# 20250808.net
KiCad netlist of a schematic drawn in EasyEDA Pro
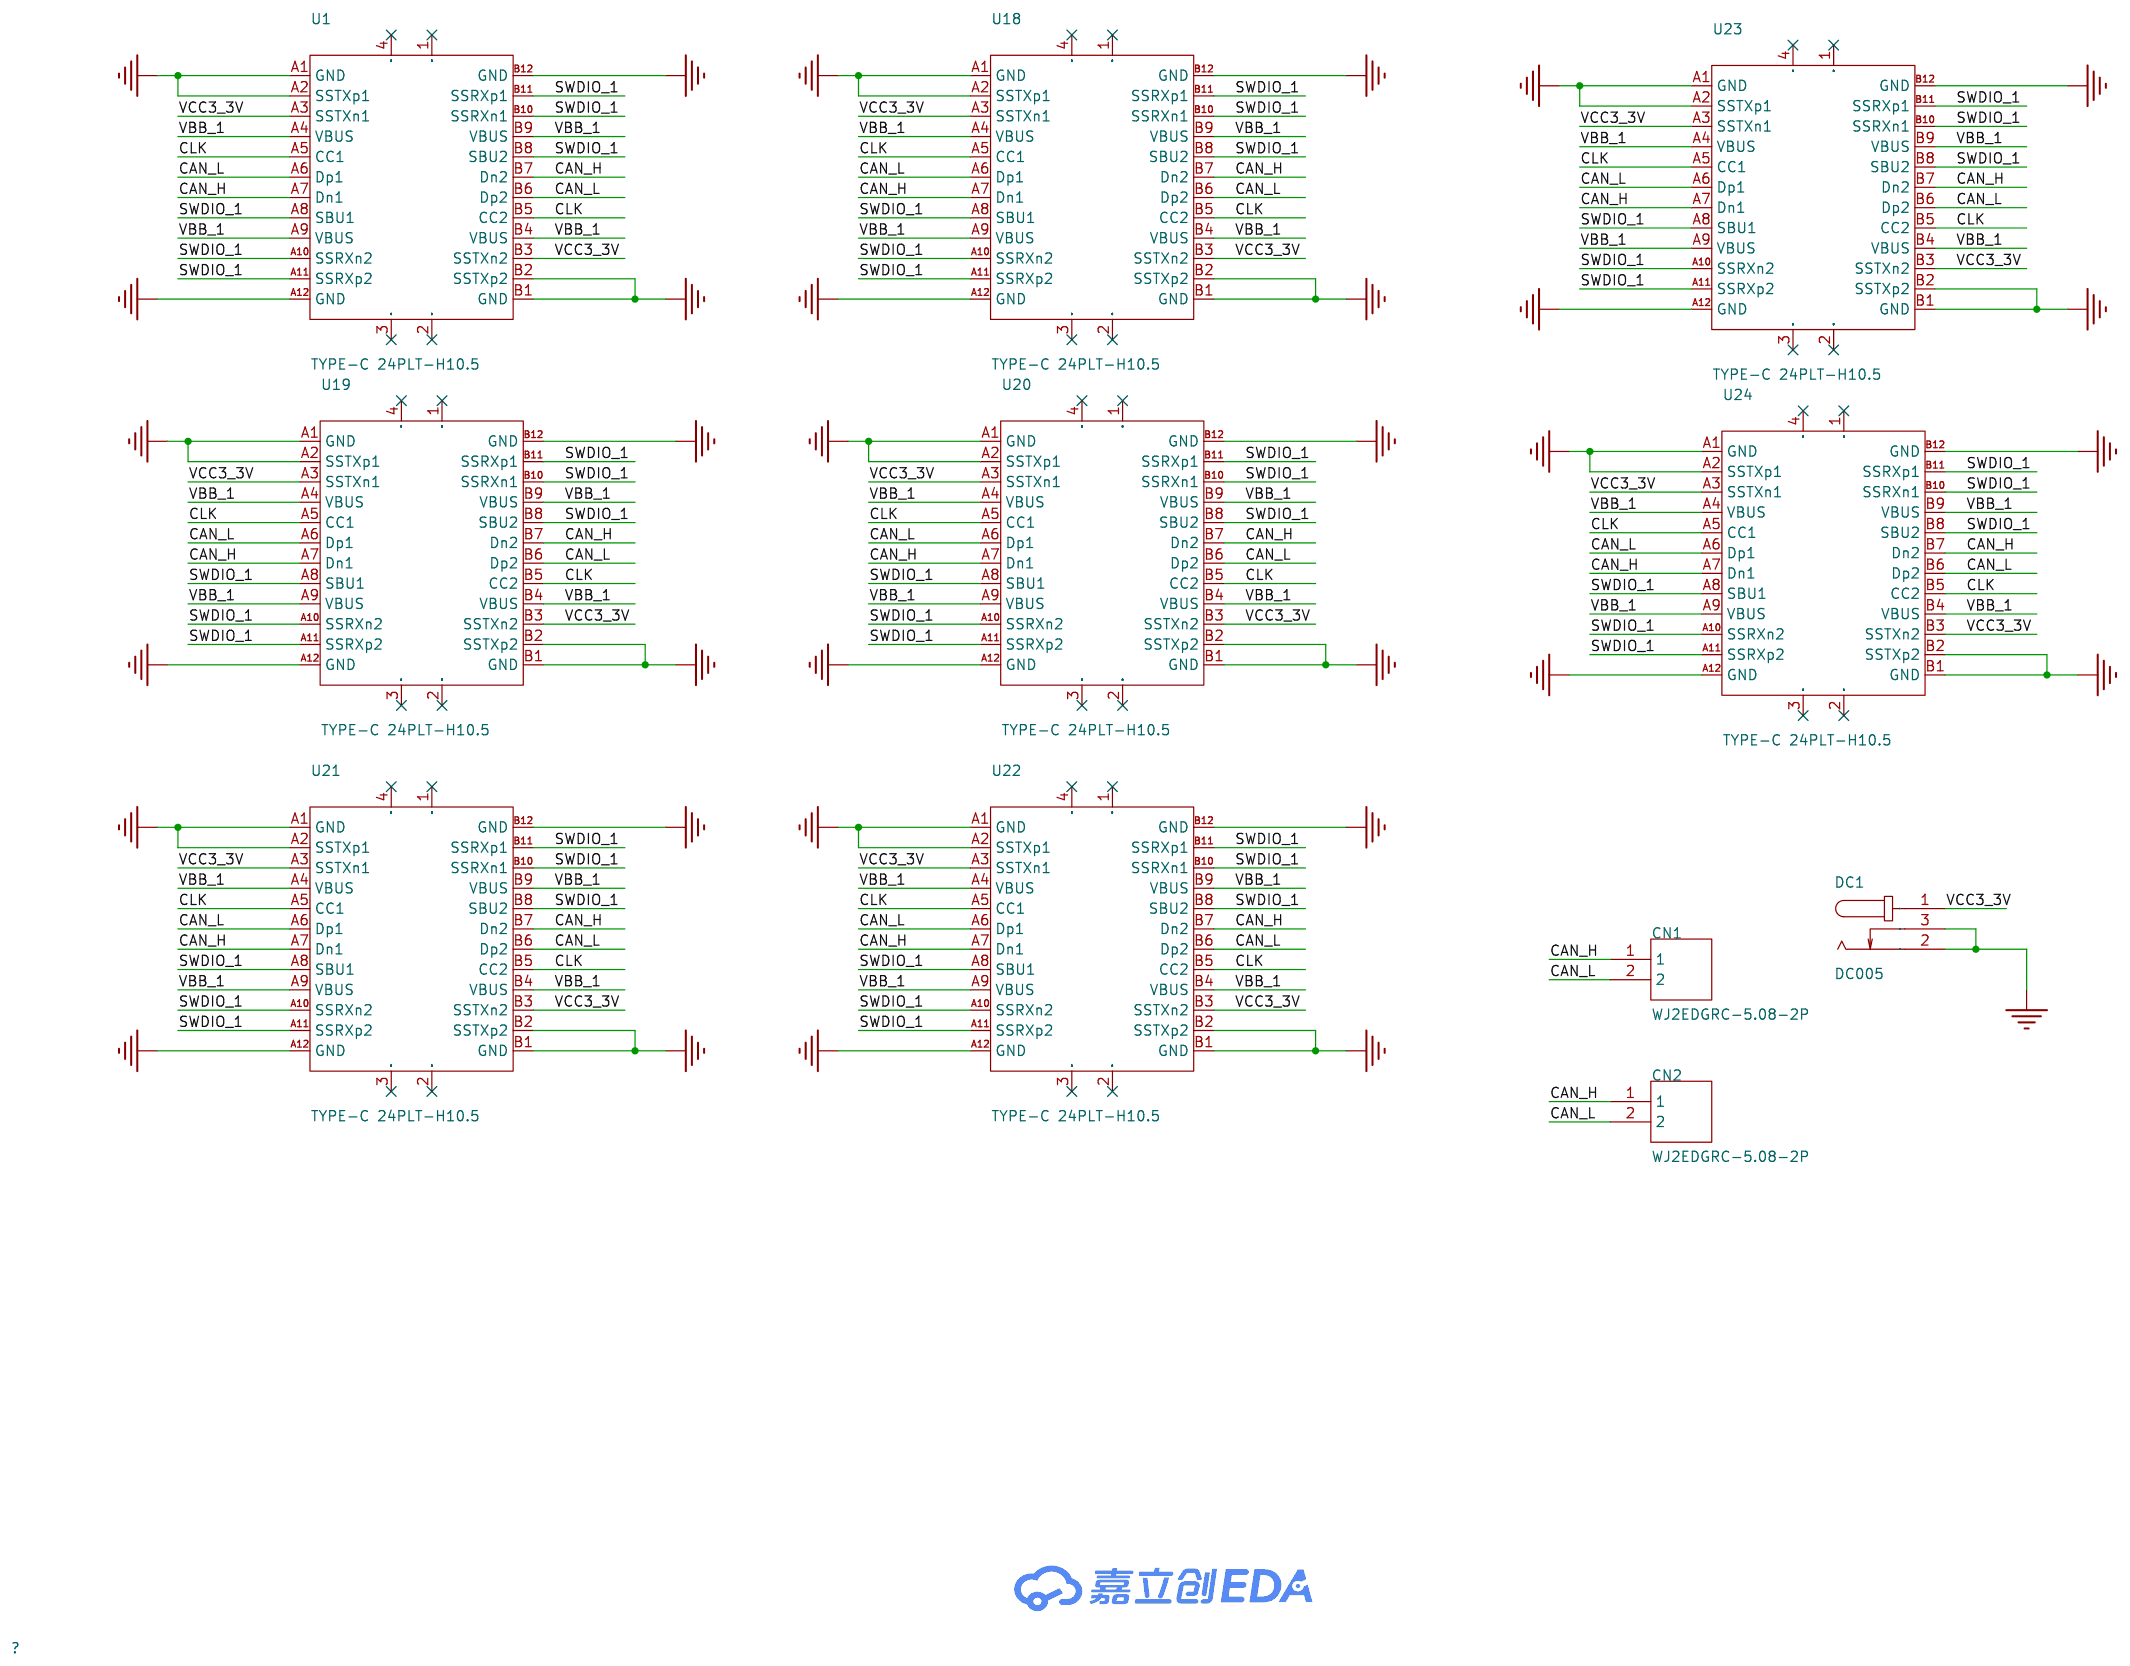
[diagram p0: schematic sheet]

(export (version "E")
  (design (tool "Eeschema 10.0.6"))
  (components
    (comp (ref "CN1")
      (value "WJ2EDGRC-5.08-2P")
      (footprint "easyedapro:CONN-TH_2P-P5.08_WJ2EDGRC-5.08-2P")
      (fields (field (name "Manufacturer") "KANGNEX(康奈克斯电气)"))
      (libsource (lib "easyedapro") (part "WJ2EDGRC-5.08-2P"))
    )
    (comp (ref "CN2")
      (value "WJ2EDGRC-5.08-2P")
      (footprint "easyedapro:CONN-TH_2P-P5.08_WJ2EDGRC-5.08-2P")
      (fields (field (name "Manufacturer") "KANGNEX(康奈克斯电气)"))
      (libsource (lib "easyedapro") (part "WJ2EDGRC-5.08-2P"))
    )
    (comp (ref "DC1")
      (value "DC005")
      (footprint "easyedapro:DC-IN-TH_DC005")
      (description "连接器类型:DC电源插座;安装方式:弯插;触点内径:2mm;触点外径:6.3mm;额定电流:500mA;额定电压:30V;工作温度范围:-25°C~+70°C;")
      (fields (field (name "Manufacturer") "SHOU HAN(首韩)"))
      (libsource (lib "easyedapro") (part "DC005_C431533"))
    )
    (comp (ref "U1")
      (value "TYPE-C 24PLT-H10.5")
      (footprint "easyedapro:USB-C_TYPE-C-24PLT-H10.5-1")
      (fields (field (name "Manufacturer") "SHOU HAN(首韩)"))
      (libsource (lib "easyedapro") (part "TYPE-C 24PLT-H10.5"))
    )
    (comp (ref "U18")
      (value "TYPE-C 24PLT-H10.5")
      (footprint "easyedapro:USB-C_TYPE-C-24PLT-H10.5-1")
      (fields (field (name "Manufacturer") "SHOU HAN(首韩)"))
      (libsource (lib "easyedapro") (part "TYPE-C 24PLT-H10.5"))
    )
    (comp (ref "U19")
      (value "TYPE-C 24PLT-H10.5")
      (footprint "easyedapro:USB-C_TYPE-C-24PLT-H10.5-1")
      (fields (field (name "Manufacturer") "SHOU HAN(首韩)"))
      (libsource (lib "easyedapro") (part "TYPE-C 24PLT-H10.5"))
    )
    (comp (ref "U20")
      (value "TYPE-C 24PLT-H10.5")
      (footprint "easyedapro:USB-C_TYPE-C-24PLT-H10.5-1")
      (fields (field (name "Manufacturer") "SHOU HAN(首韩)"))
      (libsource (lib "easyedapro") (part "TYPE-C 24PLT-H10.5"))
    )
    (comp (ref "U21")
      (value "TYPE-C 24PLT-H10.5")
      (footprint "easyedapro:USB-C_TYPE-C-24PLT-H10.5-1")
      (fields (field (name "Manufacturer") "SHOU HAN(首韩)"))
      (libsource (lib "easyedapro") (part "TYPE-C 24PLT-H10.5"))
    )
    (comp (ref "U22")
      (value "TYPE-C 24PLT-H10.5")
      (footprint "easyedapro:USB-C_TYPE-C-24PLT-H10.5-1")
      (fields (field (name "Manufacturer") "SHOU HAN(首韩)"))
      (libsource (lib "easyedapro") (part "TYPE-C 24PLT-H10.5"))
    )
    (comp (ref "U23")
      (value "TYPE-C 24PLT-H10.5")
      (footprint "easyedapro:USB-C_TYPE-C-24PLT-H10.5-1")
      (fields (field (name "Manufacturer") "SHOU HAN(首韩)"))
      (libsource (lib "easyedapro") (part "TYPE-C 24PLT-H10.5"))
    )
    (comp (ref "U24")
      (value "TYPE-C 24PLT-H10.5")
      (footprint "easyedapro:USB-C_TYPE-C-24PLT-H10.5-1")
      (fields (field (name "Manufacturer") "SHOU HAN(首韩)"))
      (libsource (lib "easyedapro") (part "TYPE-C 24PLT-H10.5"))
    )
  )
  (nets
    (net (code "1") (name "/CAN_H") (class "Default")
      (node (ref "CN1") (pin "1") (pinfunction "1_1") (pintype "unspecified"))
      (node (ref "CN2") (pin "1") (pinfunction "1_1") (pintype "unspecified"))
      (node (ref "U1") (pin "A7") (pinfunction "Dn1_A7") (pintype "unspecified"))
      (node (ref "U1") (pin "B7") (pinfunction "Dn2_B7") (pintype "unspecified"))
      (node (ref "U18") (pin "A7") (pinfunction "Dn1_A7") (pintype "unspecified"))
      (node (ref "U18") (pin "B7") (pinfunction "Dn2_B7") (pintype "unspecified"))
      (node (ref "U19") (pin "A7") (pinfunction "Dn1_A7") (pintype "unspecified"))
      (node (ref "U19") (pin "B7") (pinfunction "Dn2_B7") (pintype "unspecified"))
      (node (ref "U20") (pin "A7") (pinfunction "Dn1_A7") (pintype "unspecified"))
      (node (ref "U20") (pin "B7") (pinfunction "Dn2_B7") (pintype "unspecified"))
      (node (ref "U21") (pin "A7") (pinfunction "Dn1_A7") (pintype "unspecified"))
      (node (ref "U21") (pin "B7") (pinfunction "Dn2_B7") (pintype "unspecified"))
      (node (ref "U22") (pin "A7") (pinfunction "Dn1_A7") (pintype "unspecified"))
      (node (ref "U22") (pin "B7") (pinfunction "Dn2_B7") (pintype "unspecified"))
      (node (ref "U23") (pin "A7") (pinfunction "Dn1_A7") (pintype "unspecified"))
      (node (ref "U23") (pin "B7") (pinfunction "Dn2_B7") (pintype "unspecified"))
      (node (ref "U24") (pin "A7") (pinfunction "Dn1_A7") (pintype "unspecified"))
      (node (ref "U24") (pin "B7") (pinfunction "Dn2_B7") (pintype "unspecified"))
    )
    (net (code "2") (name "/CAN_L") (class "Default")
      (node (ref "CN1") (pin "2") (pinfunction "2_2") (pintype "unspecified"))
      (node (ref "CN2") (pin "2") (pinfunction "2_2") (pintype "unspecified"))
      (node (ref "U1") (pin "A6") (pinfunction "Dp1_A6") (pintype "unspecified"))
      (node (ref "U1") (pin "B6") (pinfunction "Dp2_B6") (pintype "unspecified"))
      (node (ref "U18") (pin "A6") (pinfunction "Dp1_A6") (pintype "unspecified"))
      (node (ref "U18") (pin "B6") (pinfunction "Dp2_B6") (pintype "unspecified"))
      (node (ref "U19") (pin "A6") (pinfunction "Dp1_A6") (pintype "unspecified"))
      (node (ref "U19") (pin "B6") (pinfunction "Dp2_B6") (pintype "unspecified"))
      (node (ref "U20") (pin "A6") (pinfunction "Dp1_A6") (pintype "unspecified"))
      (node (ref "U20") (pin "B6") (pinfunction "Dp2_B6") (pintype "unspecified"))
      (node (ref "U21") (pin "A6") (pinfunction "Dp1_A6") (pintype "unspecified"))
      (node (ref "U21") (pin "B6") (pinfunction "Dp2_B6") (pintype "unspecified"))
      (node (ref "U22") (pin "A6") (pinfunction "Dp1_A6") (pintype "unspecified"))
      (node (ref "U22") (pin "B6") (pinfunction "Dp2_B6") (pintype "unspecified"))
      (node (ref "U23") (pin "A6") (pinfunction "Dp1_A6") (pintype "unspecified"))
      (node (ref "U23") (pin "B6") (pinfunction "Dp2_B6") (pintype "unspecified"))
      (node (ref "U24") (pin "A6") (pinfunction "Dp1_A6") (pintype "unspecified"))
      (node (ref "U24") (pin "B6") (pinfunction "Dp2_B6") (pintype "unspecified"))
    )
    (net (code "3") (name "/CLK") (class "Default")
      (node (ref "U1") (pin "A5") (pinfunction "CC1_A5") (pintype "unspecified"))
      (node (ref "U1") (pin "B5") (pinfunction "CC2_B5") (pintype "unspecified"))
      (node (ref "U18") (pin "A5") (pinfunction "CC1_A5") (pintype "unspecified"))
      (node (ref "U18") (pin "B5") (pinfunction "CC2_B5") (pintype "unspecified"))
      (node (ref "U19") (pin "A5") (pinfunction "CC1_A5") (pintype "unspecified"))
      (node (ref "U19") (pin "B5") (pinfunction "CC2_B5") (pintype "unspecified"))
      (node (ref "U20") (pin "A5") (pinfunction "CC1_A5") (pintype "unspecified"))
      (node (ref "U20") (pin "B5") (pinfunction "CC2_B5") (pintype "unspecified"))
      (node (ref "U21") (pin "A5") (pinfunction "CC1_A5") (pintype "unspecified"))
      (node (ref "U21") (pin "B5") (pinfunction "CC2_B5") (pintype "unspecified"))
      (node (ref "U22") (pin "A5") (pinfunction "CC1_A5") (pintype "unspecified"))
      (node (ref "U22") (pin "B5") (pinfunction "CC2_B5") (pintype "unspecified"))
      (node (ref "U23") (pin "A5") (pinfunction "CC1_A5") (pintype "unspecified"))
      (node (ref "U23") (pin "B5") (pinfunction "CC2_B5") (pintype "unspecified"))
      (node (ref "U24") (pin "A5") (pinfunction "CC1_A5") (pintype "unspecified"))
      (node (ref "U24") (pin "B5") (pinfunction "CC2_B5") (pintype "unspecified"))
    )
    (net (code "4") (name "/SWDIO_1") (class "Default")
      (node (ref "U1") (pin "A10") (pinfunction "SSRXn2_A10") (pintype "unspecified"))
      (node (ref "U1") (pin "A11") (pinfunction "SSRXp2_A11") (pintype "unspecified"))
      (node (ref "U1") (pin "A8") (pinfunction "SBU1_A8") (pintype "unspecified"))
      (node (ref "U1") (pin "B10") (pinfunction "SSRXn1_B10") (pintype "unspecified"))
      (node (ref "U1") (pin "B11") (pinfunction "SSRXp1_B11") (pintype "unspecified"))
      (node (ref "U1") (pin "B8") (pinfunction "SBU2_B8") (pintype "unspecified"))
      (node (ref "U18") (pin "A10") (pinfunction "SSRXn2_A10") (pintype "unspecified"))
      (node (ref "U18") (pin "A11") (pinfunction "SSRXp2_A11") (pintype "unspecified"))
      (node (ref "U18") (pin "A8") (pinfunction "SBU1_A8") (pintype "unspecified"))
      (node (ref "U18") (pin "B10") (pinfunction "SSRXn1_B10") (pintype "unspecified"))
      (node (ref "U18") (pin "B11") (pinfunction "SSRXp1_B11") (pintype "unspecified"))
      (node (ref "U18") (pin "B8") (pinfunction "SBU2_B8") (pintype "unspecified"))
      (node (ref "U19") (pin "A10") (pinfunction "SSRXn2_A10") (pintype "unspecified"))
      (node (ref "U19") (pin "A11") (pinfunction "SSRXp2_A11") (pintype "unspecified"))
      (node (ref "U19") (pin "A8") (pinfunction "SBU1_A8") (pintype "unspecified"))
      (node (ref "U19") (pin "B10") (pinfunction "SSRXn1_B10") (pintype "unspecified"))
      (node (ref "U19") (pin "B11") (pinfunction "SSRXp1_B11") (pintype "unspecified"))
      (node (ref "U19") (pin "B8") (pinfunction "SBU2_B8") (pintype "unspecified"))
      (node (ref "U20") (pin "A10") (pinfunction "SSRXn2_A10") (pintype "unspecified"))
      (node (ref "U20") (pin "A11") (pinfunction "SSRXp2_A11") (pintype "unspecified"))
      (node (ref "U20") (pin "A8") (pinfunction "SBU1_A8") (pintype "unspecified"))
      (node (ref "U20") (pin "B10") (pinfunction "SSRXn1_B10") (pintype "unspecified"))
      (node (ref "U20") (pin "B11") (pinfunction "SSRXp1_B11") (pintype "unspecified"))
      (node (ref "U20") (pin "B8") (pinfunction "SBU2_B8") (pintype "unspecified"))
      (node (ref "U21") (pin "A10") (pinfunction "SSRXn2_A10") (pintype "unspecified"))
      (node (ref "U21") (pin "A11") (pinfunction "SSRXp2_A11") (pintype "unspecified"))
      (node (ref "U21") (pin "A8") (pinfunction "SBU1_A8") (pintype "unspecified"))
      (node (ref "U21") (pin "B10") (pinfunction "SSRXn1_B10") (pintype "unspecified"))
      (node (ref "U21") (pin "B11") (pinfunction "SSRXp1_B11") (pintype "unspecified"))
      (node (ref "U21") (pin "B8") (pinfunction "SBU2_B8") (pintype "unspecified"))
      (node (ref "U22") (pin "A10") (pinfunction "SSRXn2_A10") (pintype "unspecified"))
      (node (ref "U22") (pin "A11") (pinfunction "SSRXp2_A11") (pintype "unspecified"))
      (node (ref "U22") (pin "A8") (pinfunction "SBU1_A8") (pintype "unspecified"))
      (node (ref "U22") (pin "B10") (pinfunction "SSRXn1_B10") (pintype "unspecified"))
      (node (ref "U22") (pin "B11") (pinfunction "SSRXp1_B11") (pintype "unspecified"))
      (node (ref "U22") (pin "B8") (pinfunction "SBU2_B8") (pintype "unspecified"))
      (node (ref "U23") (pin "A10") (pinfunction "SSRXn2_A10") (pintype "unspecified"))
      (node (ref "U23") (pin "A11") (pinfunction "SSRXp2_A11") (pintype "unspecified"))
      (node (ref "U23") (pin "A8") (pinfunction "SBU1_A8") (pintype "unspecified"))
      (node (ref "U23") (pin "B10") (pinfunction "SSRXn1_B10") (pintype "unspecified"))
      (node (ref "U23") (pin "B11") (pinfunction "SSRXp1_B11") (pintype "unspecified"))
      (node (ref "U23") (pin "B8") (pinfunction "SBU2_B8") (pintype "unspecified"))
      (node (ref "U24") (pin "A10") (pinfunction "SSRXn2_A10") (pintype "unspecified"))
      (node (ref "U24") (pin "A11") (pinfunction "SSRXp2_A11") (pintype "unspecified"))
      (node (ref "U24") (pin "A8") (pinfunction "SBU1_A8") (pintype "unspecified"))
      (node (ref "U24") (pin "B10") (pinfunction "SSRXn1_B10") (pintype "unspecified"))
      (node (ref "U24") (pin "B11") (pinfunction "SSRXp1_B11") (pintype "unspecified"))
      (node (ref "U24") (pin "B8") (pinfunction "SBU2_B8") (pintype "unspecified"))
    )
    (net (code "5") (name "/VBB_1") (class "Default")
      (node (ref "U1") (pin "A4") (pinfunction "VBUS_A4") (pintype "unspecified"))
      (node (ref "U1") (pin "A9") (pinfunction "VBUS_A9") (pintype "unspecified"))
      (node (ref "U1") (pin "B4") (pinfunction "VBUS_B4") (pintype "unspecified"))
      (node (ref "U1") (pin "B9") (pinfunction "VBUS_B9") (pintype "unspecified"))
      (node (ref "U18") (pin "A4") (pinfunction "VBUS_A4") (pintype "unspecified"))
      (node (ref "U18") (pin "A9") (pinfunction "VBUS_A9") (pintype "unspecified"))
      (node (ref "U18") (pin "B4") (pinfunction "VBUS_B4") (pintype "unspecified"))
      (node (ref "U18") (pin "B9") (pinfunction "VBUS_B9") (pintype "unspecified"))
      (node (ref "U19") (pin "A4") (pinfunction "VBUS_A4") (pintype "unspecified"))
      (node (ref "U19") (pin "A9") (pinfunction "VBUS_A9") (pintype "unspecified"))
      (node (ref "U19") (pin "B4") (pinfunction "VBUS_B4") (pintype "unspecified"))
      (node (ref "U19") (pin "B9") (pinfunction "VBUS_B9") (pintype "unspecified"))
      (node (ref "U20") (pin "A4") (pinfunction "VBUS_A4") (pintype "unspecified"))
      (node (ref "U20") (pin "A9") (pinfunction "VBUS_A9") (pintype "unspecified"))
      (node (ref "U20") (pin "B4") (pinfunction "VBUS_B4") (pintype "unspecified"))
      (node (ref "U20") (pin "B9") (pinfunction "VBUS_B9") (pintype "unspecified"))
      (node (ref "U21") (pin "A4") (pinfunction "VBUS_A4") (pintype "unspecified"))
      (node (ref "U21") (pin "A9") (pinfunction "VBUS_A9") (pintype "unspecified"))
      (node (ref "U21") (pin "B4") (pinfunction "VBUS_B4") (pintype "unspecified"))
      (node (ref "U21") (pin "B9") (pinfunction "VBUS_B9") (pintype "unspecified"))
      (node (ref "U22") (pin "A4") (pinfunction "VBUS_A4") (pintype "unspecified"))
      (node (ref "U22") (pin "A9") (pinfunction "VBUS_A9") (pintype "unspecified"))
      (node (ref "U22") (pin "B4") (pinfunction "VBUS_B4") (pintype "unspecified"))
      (node (ref "U22") (pin "B9") (pinfunction "VBUS_B9") (pintype "unspecified"))
      (node (ref "U23") (pin "A4") (pinfunction "VBUS_A4") (pintype "unspecified"))
      (node (ref "U23") (pin "A9") (pinfunction "VBUS_A9") (pintype "unspecified"))
      (node (ref "U23") (pin "B4") (pinfunction "VBUS_B4") (pintype "unspecified"))
      (node (ref "U23") (pin "B9") (pinfunction "VBUS_B9") (pintype "unspecified"))
      (node (ref "U24") (pin "A4") (pinfunction "VBUS_A4") (pintype "unspecified"))
      (node (ref "U24") (pin "A9") (pinfunction "VBUS_A9") (pintype "unspecified"))
      (node (ref "U24") (pin "B4") (pinfunction "VBUS_B4") (pintype "unspecified"))
      (node (ref "U24") (pin "B9") (pinfunction "VBUS_B9") (pintype "unspecified"))
    )
    (net (code "6") (name "/VCC3_3V") (class "Default")
      (node (ref "DC1") (pin "1") (pinfunction "1_1") (pintype "unspecified"))
      (node (ref "U1") (pin "A3") (pinfunction "SSTXn1_A3") (pintype "unspecified"))
      (node (ref "U1") (pin "B3") (pinfunction "SSTXn2_B3") (pintype "unspecified"))
      (node (ref "U18") (pin "A3") (pinfunction "SSTXn1_A3") (pintype "unspecified"))
      (node (ref "U18") (pin "B3") (pinfunction "SSTXn2_B3") (pintype "unspecified"))
      (node (ref "U19") (pin "A3") (pinfunction "SSTXn1_A3") (pintype "unspecified"))
      (node (ref "U19") (pin "B3") (pinfunction "SSTXn2_B3") (pintype "unspecified"))
      (node (ref "U20") (pin "A3") (pinfunction "SSTXn1_A3") (pintype "unspecified"))
      (node (ref "U20") (pin "B3") (pinfunction "SSTXn2_B3") (pintype "unspecified"))
      (node (ref "U21") (pin "A3") (pinfunction "SSTXn1_A3") (pintype "unspecified"))
      (node (ref "U21") (pin "B3") (pinfunction "SSTXn2_B3") (pintype "unspecified"))
      (node (ref "U22") (pin "A3") (pinfunction "SSTXn1_A3") (pintype "unspecified"))
      (node (ref "U22") (pin "B3") (pinfunction "SSTXn2_B3") (pintype "unspecified"))
      (node (ref "U23") (pin "A3") (pinfunction "SSTXn1_A3") (pintype "unspecified"))
      (node (ref "U23") (pin "B3") (pinfunction "SSTXn2_B3") (pintype "unspecified"))
      (node (ref "U24") (pin "A3") (pinfunction "SSTXn1_A3") (pintype "unspecified"))
      (node (ref "U24") (pin "B3") (pinfunction "SSTXn2_B3") (pintype "unspecified"))
    )
    (net (code "7") (name "GND") (class "Default")
      (node (ref "DC1") (pin "2") (pinfunction "2_2") (pintype "unspecified"))
      (node (ref "DC1") (pin "3") (pinfunction "3_3") (pintype "unspecified"))
      (node (ref "U1") (pin "A1") (pinfunction "GND_A1") (pintype "unspecified"))
      (node (ref "U1") (pin "A12") (pinfunction "GND_A12") (pintype "unspecified"))
      (node (ref "U1") (pin "A2") (pinfunction "SSTXp1_A2") (pintype "unspecified"))
      (node (ref "U1") (pin "B1") (pinfunction "GND_B1") (pintype "unspecified"))
      (node (ref "U1") (pin "B12") (pinfunction "GND_B12") (pintype "unspecified"))
      (node (ref "U1") (pin "B2") (pinfunction "SSTXp2_B2") (pintype "unspecified"))
      (node (ref "U18") (pin "A1") (pinfunction "GND_A1") (pintype "unspecified"))
      (node (ref "U18") (pin "A12") (pinfunction "GND_A12") (pintype "unspecified"))
      (node (ref "U18") (pin "A2") (pinfunction "SSTXp1_A2") (pintype "unspecified"))
      (node (ref "U18") (pin "B1") (pinfunction "GND_B1") (pintype "unspecified"))
      (node (ref "U18") (pin "B12") (pinfunction "GND_B12") (pintype "unspecified"))
      (node (ref "U18") (pin "B2") (pinfunction "SSTXp2_B2") (pintype "unspecified"))
      (node (ref "U19") (pin "A1") (pinfunction "GND_A1") (pintype "unspecified"))
      (node (ref "U19") (pin "A12") (pinfunction "GND_A12") (pintype "unspecified"))
      (node (ref "U19") (pin "A2") (pinfunction "SSTXp1_A2") (pintype "unspecified"))
      (node (ref "U19") (pin "B1") (pinfunction "GND_B1") (pintype "unspecified"))
      (node (ref "U19") (pin "B12") (pinfunction "GND_B12") (pintype "unspecified"))
      (node (ref "U19") (pin "B2") (pinfunction "SSTXp2_B2") (pintype "unspecified"))
      (node (ref "U20") (pin "A1") (pinfunction "GND_A1") (pintype "unspecified"))
      (node (ref "U20") (pin "A12") (pinfunction "GND_A12") (pintype "unspecified"))
      (node (ref "U20") (pin "A2") (pinfunction "SSTXp1_A2") (pintype "unspecified"))
      (node (ref "U20") (pin "B1") (pinfunction "GND_B1") (pintype "unspecified"))
      (node (ref "U20") (pin "B12") (pinfunction "GND_B12") (pintype "unspecified"))
      (node (ref "U20") (pin "B2") (pinfunction "SSTXp2_B2") (pintype "unspecified"))
      (node (ref "U21") (pin "A1") (pinfunction "GND_A1") (pintype "unspecified"))
      (node (ref "U21") (pin "A12") (pinfunction "GND_A12") (pintype "unspecified"))
      (node (ref "U21") (pin "A2") (pinfunction "SSTXp1_A2") (pintype "unspecified"))
      (node (ref "U21") (pin "B1") (pinfunction "GND_B1") (pintype "unspecified"))
      (node (ref "U21") (pin "B12") (pinfunction "GND_B12") (pintype "unspecified"))
      (node (ref "U21") (pin "B2") (pinfunction "SSTXp2_B2") (pintype "unspecified"))
      (node (ref "U22") (pin "A1") (pinfunction "GND_A1") (pintype "unspecified"))
      (node (ref "U22") (pin "A12") (pinfunction "GND_A12") (pintype "unspecified"))
      (node (ref "U22") (pin "A2") (pinfunction "SSTXp1_A2") (pintype "unspecified"))
      (node (ref "U22") (pin "B1") (pinfunction "GND_B1") (pintype "unspecified"))
      (node (ref "U22") (pin "B12") (pinfunction "GND_B12") (pintype "unspecified"))
      (node (ref "U22") (pin "B2") (pinfunction "SSTXp2_B2") (pintype "unspecified"))
      (node (ref "U23") (pin "A1") (pinfunction "GND_A1") (pintype "unspecified"))
      (node (ref "U23") (pin "A12") (pinfunction "GND_A12") (pintype "unspecified"))
      (node (ref "U23") (pin "A2") (pinfunction "SSTXp1_A2") (pintype "unspecified"))
      (node (ref "U23") (pin "B1") (pinfunction "GND_B1") (pintype "unspecified"))
      (node (ref "U23") (pin "B12") (pinfunction "GND_B12") (pintype "unspecified"))
      (node (ref "U23") (pin "B2") (pinfunction "SSTXp2_B2") (pintype "unspecified"))
      (node (ref "U24") (pin "A1") (pinfunction "GND_A1") (pintype "unspecified"))
      (node (ref "U24") (pin "A12") (pinfunction "GND_A12") (pintype "unspecified"))
      (node (ref "U24") (pin "A2") (pinfunction "SSTXp1_A2") (pintype "unspecified"))
      (node (ref "U24") (pin "B1") (pinfunction "GND_B1") (pintype "unspecified"))
      (node (ref "U24") (pin "B12") (pinfunction "GND_B12") (pintype "unspecified"))
      (node (ref "U24") (pin "B2") (pinfunction "SSTXp2_B2") (pintype "unspecified"))
    )
    (net (code "8") (name "unconnected-(U1-SHEELD-Pad1)") (class "Default")
      (node (ref "U1") (pin "1") (pinfunction "SHEELD_1") (pintype "unspecified+no_connect"))
    )
    (net (code "9") (name "unconnected-(U1-SHEELD-Pad2)") (class "Default")
      (node (ref "U1") (pin "2") (pinfunction "SHEELD_2") (pintype "unspecified+no_connect"))
    )
    (net (code "10") (name "unconnected-(U1-SHEELD-Pad3)") (class "Default")
      (node (ref "U1") (pin "3") (pinfunction "SHEELD_3") (pintype "unspecified+no_connect"))
    )
    (net (code "11") (name "unconnected-(U1-SHEELD-Pad4)") (class "Default")
      (node (ref "U1") (pin "4") (pinfunction "SHEELD_4") (pintype "unspecified+no_connect"))
    )
    (net (code "12") (name "unconnected-(U18-SHEELD-Pad1)") (class "Default")
      (node (ref "U18") (pin "1") (pinfunction "SHEELD_1") (pintype "unspecified+no_connect"))
    )
    (net (code "13") (name "unconnected-(U18-SHEELD-Pad2)") (class "Default")
      (node (ref "U18") (pin "2") (pinfunction "SHEELD_2") (pintype "unspecified+no_connect"))
    )
    (net (code "14") (name "unconnected-(U18-SHEELD-Pad3)") (class "Default")
      (node (ref "U18") (pin "3") (pinfunction "SHEELD_3") (pintype "unspecified+no_connect"))
    )
    (net (code "15") (name "unconnected-(U18-SHEELD-Pad4)") (class "Default")
      (node (ref "U18") (pin "4") (pinfunction "SHEELD_4") (pintype "unspecified+no_connect"))
    )
    (net (code "16") (name "unconnected-(U19-SHEELD-Pad1)") (class "Default")
      (node (ref "U19") (pin "1") (pinfunction "SHEELD_1") (pintype "unspecified+no_connect"))
    )
    (net (code "17") (name "unconnected-(U19-SHEELD-Pad2)") (class "Default")
      (node (ref "U19") (pin "2") (pinfunction "SHEELD_2") (pintype "unspecified+no_connect"))
    )
    (net (code "18") (name "unconnected-(U19-SHEELD-Pad3)") (class "Default")
      (node (ref "U19") (pin "3") (pinfunction "SHEELD_3") (pintype "unspecified+no_connect"))
    )
    (net (code "19") (name "unconnected-(U19-SHEELD-Pad4)") (class "Default")
      (node (ref "U19") (pin "4") (pinfunction "SHEELD_4") (pintype "unspecified+no_connect"))
    )
    (net (code "20") (name "unconnected-(U20-SHEELD-Pad1)") (class "Default")
      (node (ref "U20") (pin "1") (pinfunction "SHEELD_1") (pintype "unspecified+no_connect"))
    )
    (net (code "21") (name "unconnected-(U20-SHEELD-Pad2)") (class "Default")
      (node (ref "U20") (pin "2") (pinfunction "SHEELD_2") (pintype "unspecified+no_connect"))
    )
    (net (code "22") (name "unconnected-(U20-SHEELD-Pad3)") (class "Default")
      (node (ref "U20") (pin "3") (pinfunction "SHEELD_3") (pintype "unspecified+no_connect"))
    )
    (net (code "23") (name "unconnected-(U20-SHEELD-Pad4)") (class "Default")
      (node (ref "U20") (pin "4") (pinfunction "SHEELD_4") (pintype "unspecified+no_connect"))
    )
    (net (code "24") (name "unconnected-(U21-SHEELD-Pad1)") (class "Default")
      (node (ref "U21") (pin "1") (pinfunction "SHEELD_1") (pintype "unspecified+no_connect"))
    )
    (net (code "25") (name "unconnected-(U21-SHEELD-Pad2)") (class "Default")
      (node (ref "U21") (pin "2") (pinfunction "SHEELD_2") (pintype "unspecified+no_connect"))
    )
    (net (code "26") (name "unconnected-(U21-SHEELD-Pad3)") (class "Default")
      (node (ref "U21") (pin "3") (pinfunction "SHEELD_3") (pintype "unspecified+no_connect"))
    )
    (net (code "27") (name "unconnected-(U21-SHEELD-Pad4)") (class "Default")
      (node (ref "U21") (pin "4") (pinfunction "SHEELD_4") (pintype "unspecified+no_connect"))
    )
    (net (code "28") (name "unconnected-(U22-SHEELD-Pad1)") (class "Default")
      (node (ref "U22") (pin "1") (pinfunction "SHEELD_1") (pintype "unspecified+no_connect"))
    )
    (net (code "29") (name "unconnected-(U22-SHEELD-Pad2)") (class "Default")
      (node (ref "U22") (pin "2") (pinfunction "SHEELD_2") (pintype "unspecified+no_connect"))
    )
    (net (code "30") (name "unconnected-(U22-SHEELD-Pad3)") (class "Default")
      (node (ref "U22") (pin "3") (pinfunction "SHEELD_3") (pintype "unspecified+no_connect"))
    )
    (net (code "31") (name "unconnected-(U22-SHEELD-Pad4)") (class "Default")
      (node (ref "U22") (pin "4") (pinfunction "SHEELD_4") (pintype "unspecified+no_connect"))
    )
    (net (code "32") (name "unconnected-(U23-SHEELD-Pad1)") (class "Default")
      (node (ref "U23") (pin "1") (pinfunction "SHEELD_1") (pintype "unspecified+no_connect"))
    )
    (net (code "33") (name "unconnected-(U23-SHEELD-Pad2)") (class "Default")
      (node (ref "U23") (pin "2") (pinfunction "SHEELD_2") (pintype "unspecified+no_connect"))
    )
    (net (code "34") (name "unconnected-(U23-SHEELD-Pad3)") (class "Default")
      (node (ref "U23") (pin "3") (pinfunction "SHEELD_3") (pintype "unspecified+no_connect"))
    )
    (net (code "35") (name "unconnected-(U23-SHEELD-Pad4)") (class "Default")
      (node (ref "U23") (pin "4") (pinfunction "SHEELD_4") (pintype "unspecified+no_connect"))
    )
    (net (code "36") (name "unconnected-(U24-SHEELD-Pad1)") (class "Default")
      (node (ref "U24") (pin "1") (pinfunction "SHEELD_1") (pintype "unspecified+no_connect"))
    )
    (net (code "37") (name "unconnected-(U24-SHEELD-Pad2)") (class "Default")
      (node (ref "U24") (pin "2") (pinfunction "SHEELD_2") (pintype "unspecified+no_connect"))
    )
    (net (code "38") (name "unconnected-(U24-SHEELD-Pad3)") (class "Default")
      (node (ref "U24") (pin "3") (pinfunction "SHEELD_3") (pintype "unspecified+no_connect"))
    )
    (net (code "39") (name "unconnected-(U24-SHEELD-Pad4)") (class "Default")
      (node (ref "U24") (pin "4") (pinfunction "SHEELD_4") (pintype "unspecified+no_connect"))
    )
  )
)
